# 7_dc_dc_3v3_ant_obdh.net
KiCad netlist of a schematic drawn in Altium Designer
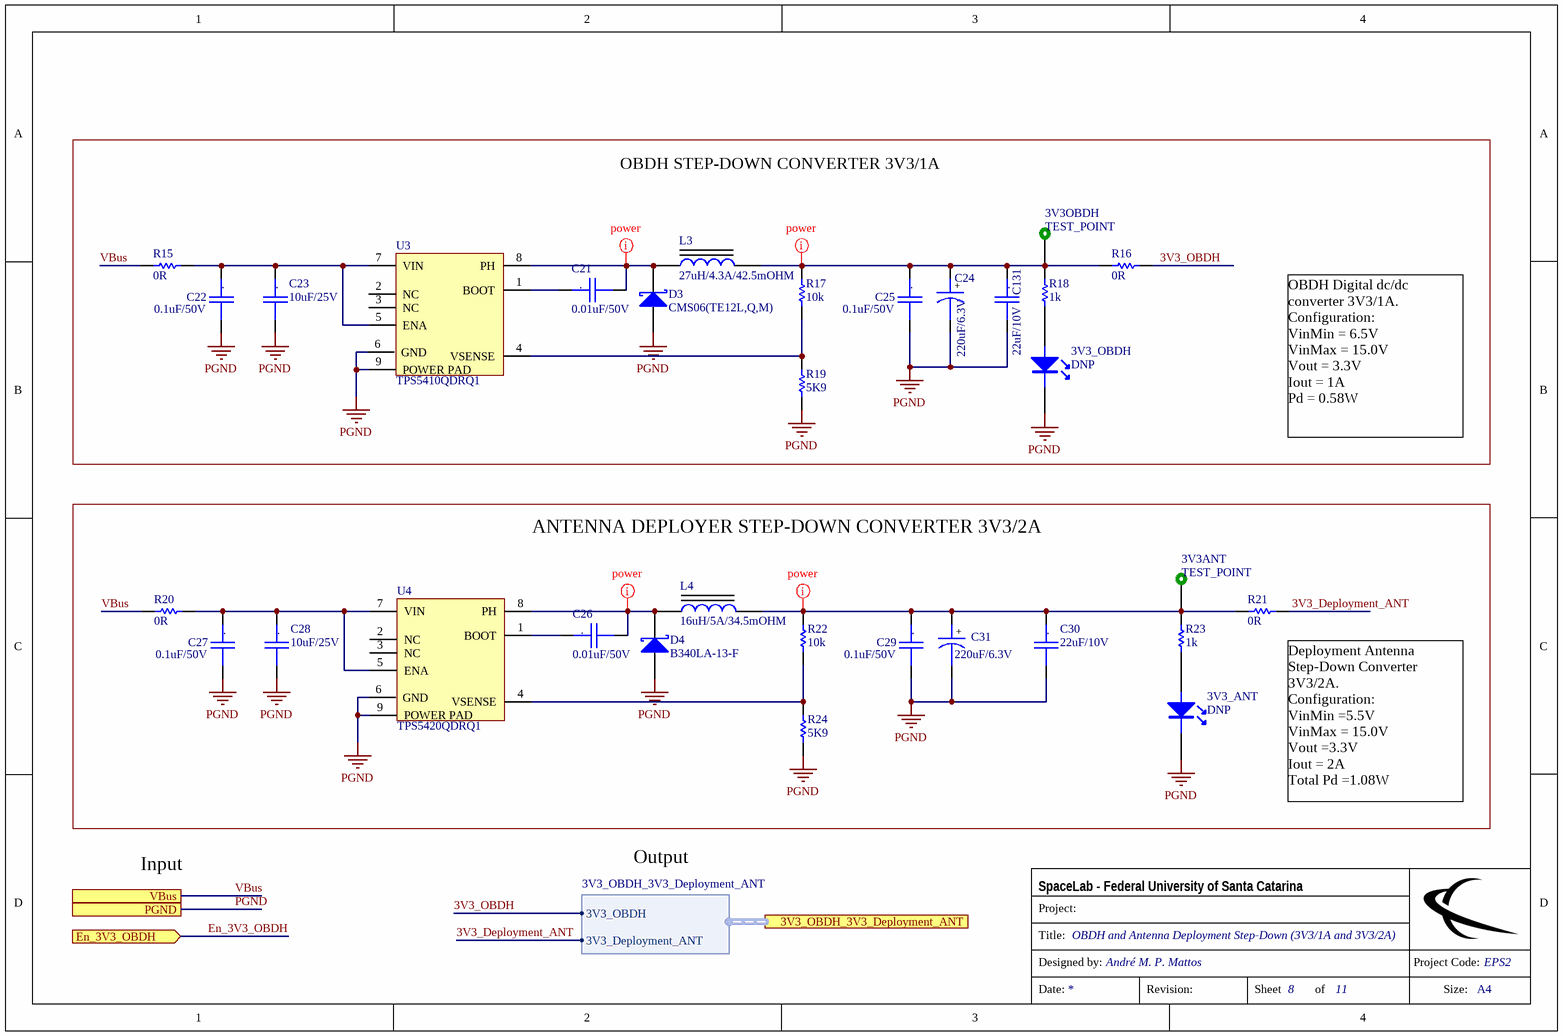
[diagram p0: 7_dc_dc_3v3_ant_obdh.schdoc]

(export (version "E")
  (design (tool "Eeschema 10.0.6"))
  (components
    (comp (ref "3V3ANT")
      (value "TEST_POINT")
      (footprint "TEST_POINT")
      (description "Test point")
      (libsource (lib "PCB_Project_FlightModel_EPS") (part "TEST_POINT"))
    )
    (comp (ref "3V3OBDH")
      (value "TEST_POINT")
      (footprint "TEST_POINT")
      (description "Test point")
      (libsource (lib "PCB_Project_FlightModel_EPS") (part "TEST_POINT"))
    )
    (comp (ref "3V3_ANT")
      (value "DNP")
      (footprint "0603-LED")
      (description "SMD Green LED")
      (fields (field (name "PARTNUMBER") "150060VS75000") (field (name "MANUFACTURER") "Wurth Electronics"))
      (libsource (lib "PCB_Project_FlightModel_EPS") (part "LED/G_0603"))
    )
    (comp (ref "3V3_OBDH")
      (value "DNP")
      (footprint "0603-LED")
      (description "SMD Green LED")
      (fields (field (name "PARTNUMBER") "150060VS75000") (field (name "MANUFACTURER") "Wurth Electronics"))
      (libsource (lib "PCB_Project_FlightModel_EPS") (part "LED/G_0603"))
    )
    (comp (ref "C21")
      (value "0.01uF/50V")
      (footprint "CC0805")
      (description "CAP CER 0.01uF 50V 10% X7R 0805")
      (fields (field (name "PARTNUMBER") "08055C103KAT4A") (field (name "MANUFACTURER") "Kyocera AVX"))
      (libsource (lib "PCB_Project_FlightModel_EPS") (part "Cap_Cer_X7R_0.01uF_50V_0805"))
    )
    (comp (ref "C22")
      (value "0.1uF/50V")
      (footprint "CC0805")
      (description "CAP CER 0.1UF 50V 10% X7R 0805")
      (fields (field (name "PARTNUMBER") "CC0805KRX7R9BB104") (field (name "MANUFACTURER") "Yageo"))
      (libsource (lib "PCB_Project_FlightModel_EPS") (part "Cap_Cer_X7R_0.1uF_50V_0805"))
    )
    (comp (ref "C23")
      (value "10uF/25V")
      (footprint "CC1206")
      (description "CAP CER 10uF 25V 10% X7R 1206")
      (fields (field (name "PARTNUMBER") "GRM31CR71E106KA12L") (field (name "MANUFACTURER") "Murata"))
      (libsource (lib "PCB_Project_FlightModel_EPS") (part "Cap_Cer_X7R_10uF_25V_1206"))
    )
    (comp (ref "C24")
      (value "220uF/6.3V")
      (footprint "FloripaSatPcbLib:cc1210")
      (description "CAP Tantalum 220uF 6.3V 20% 1210")
      (fields (field (name "PARTNUMBER") "6TPE220MAZB") (field (name "MANUFACTURER") "Panasonic"))
      (libsource (lib "PCB_Project_FlightModel_EPS") (part "Cap_Tant_SMD_220uF_6.3V_1210"))
    )
    (comp (ref "C25")
      (value "0.1uF/50V")
      (footprint "CC0805")
      (description "CAP CER 0.1UF 50V 10% X7R 0805")
      (fields (field (name "PARTNUMBER") "CC0805KRX7R9BB104") (field (name "MANUFACTURER") "Yageo"))
      (libsource (lib "PCB_Project_FlightModel_EPS") (part "Cap_Cer_X7R_0.1uF_50V_0805"))
    )
    (comp (ref "C26")
      (value "0.01uF/50V")
      (footprint "CC0805")
      (description "CAP CER 0.01uF 50V 10% X7R 0805")
      (fields (field (name "PARTNUMBER") "08055C103KAT4A") (field (name "MANUFACTURER") "Kyocera AVX"))
      (libsource (lib "PCB_Project_FlightModel_EPS") (part "Cap_Cer_X7R_0.01uF_50V_0805"))
    )
    (comp (ref "C27")
      (value "0.1uF/50V")
      (footprint "CC0805")
      (description "CAP CER 0.1UF 50V 10% X7R 0805")
      (fields (field (name "PARTNUMBER") "CC0805KRX7R9BB104") (field (name "MANUFACTURER") "Yageo"))
      (libsource (lib "PCB_Project_FlightModel_EPS") (part "Cap_Cer_X7R_0.1uF_50V_0805"))
    )
    (comp (ref "C28")
      (value "10uF/25V")
      (footprint "CC1206")
      (description "CAP CER 10uF 25V 10% X7R 1206")
      (fields (field (name "PARTNUMBER") "GRM31CR71E106KA12L") (field (name "MANUFACTURER") "Murata"))
      (libsource (lib "PCB_Project_FlightModel_EPS") (part "Cap_Cer_X7R_10uF_25V_1206"))
    )
    (comp (ref "C29")
      (value "0.1uF/50V")
      (footprint "CC0805")
      (description "CAP CER 0.1UF 50V 10% X7R 0805")
      (fields (field (name "PARTNUMBER") "CC0805KRX7R9BB104") (field (name "MANUFACTURER") "Yageo"))
      (libsource (lib "PCB_Project_FlightModel_EPS") (part "Cap_Cer_X7R_0.1uF_50V_0805"))
    )
    (comp (ref "C30")
      (value "22uF/10V")
      (footprint "CC1206")
      (description "CAP CER 22uF 10V 10% X7R 1206")
      (fields (field (name "PARTNUMBER") "GRM31CR71A226KE15L") (field (name "MANUFACTURER") "Murata"))
      (libsource (lib "PCB_Project_FlightModel_EPS") (part "Cap_Cer_X7R_22uF_10V_1206"))
    )
    (comp (ref "C31")
      (value "220uF/6.3V")
      (footprint "FloripaSatPcbLib:cc1210")
      (description "CAP Tantalum 220uF 6.3V 20% 1210")
      (fields (field (name "PARTNUMBER") "6TPE220MAZB") (field (name "MANUFACTURER") "Panasonic"))
      (libsource (lib "PCB_Project_FlightModel_EPS") (part "Cap_Tant_SMD_220uF_6.3V_1210"))
    )
    (comp (ref "C131")
      (value "22uF/10V")
      (footprint "CC1206")
      (description "CAP CER 22uF 10V 10% X7R 1206")
      (fields (field (name "PARTNUMBER") "GRM31CR71A226KE15L") (field (name "MANUFACTURER") "Murata"))
      (libsource (lib "PCB_Project_FlightModel_EPS") (part "Cap_Cer_X7R_22uF_10V_1206"))
    )
    (comp (ref "D3")
      (value "CMS06(TE12L,Q,M)")
      (footprint "cms06")
      (description "DIODE SCHOTTKY 30V 2A   CMS06(TE12L,Q,M)")
      (fields (field (name "MANUFACTURER") "Toshiba"))
      (libsource (lib "PCB_Project_FlightModel_EPS") (part "DIODE_SCHOTTKY_30V_2A_  CMS06(TE12L,Q,M)"))
    )
    (comp (ref "D4")
      (value "B340LA-13-F")
      (footprint "DO-214AC")
      (description "DIODE SCHOTTKY 40V 3A B340LA-13-F")
      (fields (field (name "MANUFACTURER") "Diodes"))
      (libsource (lib "PCB_Project_FlightModel_EPS") (part "DIODE_SCHOTTKY_40V_3A_B340LA-13-F"))
    )
    (comp (ref "L3")
      (value "27uH/4.3A/42.5mOHM")
      (footprint "IND_744325xxx")
      (description "INDUCTOR 27UH 4.3A SMD")
      (fields (field (name "PARTNUMBER") "7447798271") (field (name "MANUFACTURER") "Wurth Electronics"))
      (libsource (lib "PCB_Project_FlightModel_EPS") (part "IND_POWER_27uH_4.3A_42.5mR"))
    )
    (comp (ref "L4")
      (value "16uH/5A/34.5mOHM")
      (footprint "IND_744325xxx")
      (description "INDUCTOR 16UH 5A SMD")
      (fields (field (name "PARTNUMBER") "7443251600") (field (name "MANUFACTURER") "Wurth Electronics"))
      (libsource (lib "PCB_Project_FlightModel_EPS") (part "IND_POWER_16uH_5A_35.5mR"))
    )
    (comp (ref "R15")
      (value "0R")
      (footprint "1206")
      (description "RES 0.0 OHM 3/4W JUMP 1206")
      (fields
        (field (name "PARTNUMBER") "HCJ1206ZT0R00")
        (field (name "MANUFACTURER") "Stackpole Electronics")
      )
      (libsource (lib "PCB_Project_FlightModel_EPS") (part "R0R_JUMPER_3/4W_1206"))
    )
    (comp (ref "R16")
      (value "0R")
      (footprint "1206")
      (description "RES 0.0 OHM 3/4W JUMP 1206")
      (fields
        (field (name "PARTNUMBER") "HCJ1206ZT0R00")
        (field (name "MANUFACTURER") "Stackpole Electronics")
      )
      (libsource (lib "PCB_Project_FlightModel_EPS") (part "R0R_JUMPER_3/4W_1206"))
    )
    (comp (ref "R17")
      (value "10k")
      (footprint "0805")
      (description "RES 10K OHM 1/8W 1%  0805")
      (fields (field (name "PARTNUMBER") "CRCW080510K0FKEA") (field (name "MANUFACTURER") "Vishay"))
      (libsource (lib "PCB_Project_FlightModel_EPS") (part "R10k_1%_1/8W_0805"))
    )
    (comp (ref "R18")
      (value "1k")
      (footprint "0603")
      (description "RES 1.0K OHM 1/8W 1% 0603")
      (fields (field (name "PARTNUMBER") "MCT06030C1001FP500") (field (name "MANUFACTURER") "Vishay"))
      (libsource (lib "PCB_Project_FlightModel_EPS") (part "R1.0k_1%_1/8W_0603"))
    )
    (comp (ref "R19")
      (value "5K9")
      (footprint "0805")
      (description "RES 5K9 OHM 1/8W 1% 0805")
      (fields (field (name "PARTNUMBER") "71-CRCW0805-5.9K-E3") (field (name "MANUFACTURER") "Vishay"))
      (libsource (lib "PCB_Project_FlightModel_EPS") (part "R5.9K_1%_1/8W_0805"))
    )
    (comp (ref "R20")
      (value "0R")
      (footprint "1206")
      (description "RES 0.0 OHM 3/4W JUMP 1206")
      (fields
        (field (name "PARTNUMBER") "HCJ1206ZT0R00")
        (field (name "MANUFACTURER") "Stackpole Electronics")
      )
      (libsource (lib "PCB_Project_FlightModel_EPS") (part "R0R_JUMPER_3/4W_1206"))
    )
    (comp (ref "R21")
      (value "0R")
      (footprint "1206")
      (description "RES 0.0 OHM 3/4W JUMP 1206")
      (fields
        (field (name "PARTNUMBER") "HCJ1206ZT0R00")
        (field (name "MANUFACTURER") "Stackpole Electronics")
      )
      (libsource (lib "PCB_Project_FlightModel_EPS") (part "R0R_JUMPER_3/4W_1206"))
    )
    (comp (ref "R22")
      (value "10k")
      (footprint "0805")
      (description "RES 10K OHM 1/8W 1%  0805")
      (fields (field (name "PARTNUMBER") "CRCW080510K0FKEA") (field (name "MANUFACTURER") "Vishay"))
      (libsource (lib "PCB_Project_FlightModel_EPS") (part "R10k_1%_1/8W_0805"))
    )
    (comp (ref "R23")
      (value "1k")
      (footprint "0603")
      (description "RES 1.0K OHM 1/8W 1% 0603")
      (fields (field (name "PARTNUMBER") "MCT06030C1001FP500") (field (name "MANUFACTURER") "Vishay"))
      (libsource (lib "PCB_Project_FlightModel_EPS") (part "R1.0k_1%_1/8W_0603"))
    )
    (comp (ref "R24")
      (value "5K9")
      (footprint "0805")
      (description "RES 5K9 OHM 1/8W 1% 0805")
      (fields (field (name "PARTNUMBER") "71-CRCW0805-5.9K-E3") (field (name "MANUFACTURER") "Vishay"))
      (libsource (lib "PCB_Project_FlightModel_EPS") (part "R5.9K_1%_1/8W_0805"))
    )
    (comp (ref "U3")
      (value "TPS5410QDRQ1")
      (footprint "SO8 Power PAD")
      (fields (field (name "MANUFACTURER") "Texas Instruments"))
      (libsource (lib "PCB_Project_FlightModel_EPS") (part "TPS5410QDRQ1"))
    )
    (comp (ref "U4")
      (value "TPS5420QDRQ1")
      (footprint "SO8 Power PAD")
      (fields (field (name "MANUFACTURER") "Texas Instruments"))
      (libsource (lib "PCB_Project_FlightModel_EPS") (part "TPS5420QDRQ1"))
    )
  )
  (nets
    (net (code "2") (name "/3V3_Deployment_ANT") (class "Default")
      (node (ref "R21") (pin "1") (pinfunction "1_1") (pintype "passive"))
    )
    (net (code "3") (name "/3V3_OBDH") (class "Default")
      (node (ref "R16") (pin "1") (pinfunction "1_1") (pintype "passive"))
    )
    (net (code "5") (name "/VBus") (class "Default")
      (node (ref "R15") (pin "2") (pinfunction "2_2") (pintype "passive"))
      (node (ref "R20") (pin "2") (pinfunction "2_2") (pintype "passive"))
    )
    (net (code "7") (name "Net-(3V3ANT-Pad1)") (class "Default")
      (node (ref "3V3ANT") (pin "1") (pinfunction "1_1") (pintype "passive"))
      (node (ref "C29") (pin "1") (pinfunction "1_1") (pintype "passive"))
      (node (ref "C30") (pin "1") (pinfunction "1_1") (pintype "passive"))
      (node (ref "C31") (pin "1") (pinfunction "1_1") (pintype "passive"))
      (node (ref "L4") (pin "2") (pinfunction "2_2") (pintype "passive"))
      (node (ref "R21") (pin "2") (pinfunction "2_2") (pintype "passive"))
      (node (ref "R22") (pin "2") (pinfunction "2_2") (pintype "passive"))
      (node (ref "R23") (pin "1") (pinfunction "1_1") (pintype "passive"))
    )
    (net (code "8") (name "Net-(3V3OBDH-Pad1)") (class "Default")
      (node (ref "3V3OBDH") (pin "1") (pinfunction "1_1") (pintype "passive"))
      (node (ref "C131") (pin "1") (pinfunction "1_1") (pintype "passive"))
      (node (ref "C24") (pin "1") (pinfunction "1_1") (pintype "passive"))
      (node (ref "C25") (pin "1") (pinfunction "1_1") (pintype "passive"))
      (node (ref "L3") (pin "2") (pinfunction "2_2") (pintype "passive"))
      (node (ref "R16") (pin "2") (pinfunction "2_2") (pintype "passive"))
      (node (ref "R17") (pin "2") (pinfunction "2_2") (pintype "passive"))
      (node (ref "R18") (pin "1") (pinfunction "1_1") (pintype "passive"))
    )
    (net (code "9") (name "Net-(3V3_ANT-A)") (class "Default")
      (node (ref "3V3_ANT") (pin "1") (pinfunction "A_1") (pintype "passive"))
      (node (ref "R23") (pin "2") (pinfunction "2_2") (pintype "passive"))
    )
    (net (code "10") (name "Net-(3V3_OBDH-A)") (class "Default")
      (node (ref "3V3_OBDH") (pin "1") (pinfunction "A_1") (pintype "passive"))
      (node (ref "R18") (pin "2") (pinfunction "2_2") (pintype "passive"))
    )
    (net (code "11") (name "Net-(D3-K)") (class "Default")
      (node (ref "C21") (pin "2") (pinfunction "2_2") (pintype "passive"))
      (node (ref "D3") (pin "1") (pinfunction "K_1") (pintype "passive"))
      (node (ref "L3") (pin "1") (pinfunction "1_1") (pintype "passive"))
      (node (ref "U3") (pin "8") (pinfunction "PH_8") (pintype "passive"))
    )
    (net (code "12") (name "Net-(D4-K)") (class "Default")
      (node (ref "C26") (pin "2") (pinfunction "2_2") (pintype "passive"))
      (node (ref "D4") (pin "1") (pinfunction "K_1") (pintype "passive"))
      (node (ref "L4") (pin "1") (pinfunction "1_1") (pintype "passive"))
      (node (ref "U4") (pin "8") (pinfunction "PH_8") (pintype "passive"))
    )
    (net (code "13") (name "Net-(U3-BOOT)") (class "Default")
      (node (ref "C21") (pin "1") (pinfunction "1_1") (pintype "passive"))
      (node (ref "U3") (pin "1") (pinfunction "BOOT_1") (pintype "passive"))
    )
    (net (code "14") (name "Net-(U3-ENA)") (class "Default")
      (node (ref "C22") (pin "1") (pinfunction "1_1") (pintype "passive"))
      (node (ref "C23") (pin "1") (pinfunction "1_1") (pintype "passive"))
      (node (ref "R15") (pin "1") (pinfunction "1_1") (pintype "passive"))
      (node (ref "U3") (pin "5") (pinfunction "ENA_5") (pintype "passive"))
      (node (ref "U3") (pin "7") (pinfunction "VIN_7") (pintype "passive"))
    )
    (net (code "15") (name "Net-(U3-VSENSE)") (class "Default")
      (node (ref "R17") (pin "1") (pinfunction "1_1") (pintype "passive"))
      (node (ref "R19") (pin "2") (pinfunction "2_2") (pintype "passive"))
      (node (ref "U3") (pin "4") (pinfunction "VSENSE_4") (pintype "passive"))
    )
    (net (code "16") (name "Net-(U4-BOOT)") (class "Default")
      (node (ref "C26") (pin "1") (pinfunction "1_1") (pintype "passive"))
      (node (ref "U4") (pin "1") (pinfunction "BOOT_1") (pintype "passive"))
    )
    (net (code "17") (name "Net-(U4-ENA)") (class "Default")
      (node (ref "C27") (pin "1") (pinfunction "1_1") (pintype "passive"))
      (node (ref "C28") (pin "1") (pinfunction "1_1") (pintype "passive"))
      (node (ref "R20") (pin "1") (pinfunction "1_1") (pintype "passive"))
      (node (ref "U4") (pin "5") (pinfunction "ENA_5") (pintype "passive"))
      (node (ref "U4") (pin "7") (pinfunction "VIN_7") (pintype "passive"))
    )
    (net (code "18") (name "Net-(U4-VSENSE)") (class "Default")
      (node (ref "R22") (pin "1") (pinfunction "1_1") (pintype "passive"))
      (node (ref "R24") (pin "2") (pinfunction "2_2") (pintype "passive"))
      (node (ref "U4") (pin "4") (pinfunction "VSENSE_4") (pintype "passive"))
    )
    (net (code "19") (name "PGND") (class "Default")
      (node (ref "3V3_ANT") (pin "2") (pinfunction "K_2") (pintype "passive"))
      (node (ref "3V3_OBDH") (pin "2") (pinfunction "K_2") (pintype "passive"))
      (node (ref "C131") (pin "2") (pinfunction "2_2") (pintype "passive"))
      (node (ref "C22") (pin "2") (pinfunction "2_2") (pintype "passive"))
      (node (ref "C23") (pin "2") (pinfunction "2_2") (pintype "passive"))
      (node (ref "C24") (pin "2") (pinfunction "2_2") (pintype "passive"))
      (node (ref "C25") (pin "2") (pinfunction "2_2") (pintype "passive"))
      (node (ref "C27") (pin "2") (pinfunction "2_2") (pintype "passive"))
      (node (ref "C28") (pin "2") (pinfunction "2_2") (pintype "passive"))
      (node (ref "C29") (pin "2") (pinfunction "2_2") (pintype "passive"))
      (node (ref "C30") (pin "2") (pinfunction "2_2") (pintype "passive"))
      (node (ref "C31") (pin "2") (pinfunction "2_2") (pintype "passive"))
      (node (ref "D3") (pin "2") (pinfunction "A_2") (pintype "passive"))
      (node (ref "D4") (pin "2") (pinfunction "A_2") (pintype "passive"))
      (node (ref "R19") (pin "1") (pinfunction "1_1") (pintype "passive"))
      (node (ref "R24") (pin "1") (pinfunction "1_1") (pintype "passive"))
      (node (ref "U3") (pin "6") (pinfunction "GND_6") (pintype "passive"))
      (node (ref "U3") (pin "9") (pinfunction "POWER_PAD_9") (pintype "passive"))
      (node (ref "U4") (pin "6") (pinfunction "GND_6") (pintype "passive"))
      (node (ref "U4") (pin "9") (pinfunction "POWER_PAD_9") (pintype "passive"))
    )
    (net (code "20") (name "unconnected-(U3-NC-Pad2)") (class "Default")
      (node (ref "U3") (pin "2") (pinfunction "NC_2") (pintype "passive"))
    )
    (net (code "21") (name "unconnected-(U3-NC-Pad3)") (class "Default")
      (node (ref "U3") (pin "3") (pinfunction "NC_3") (pintype "passive"))
    )
    (net (code "22") (name "unconnected-(U4-NC-Pad2)") (class "Default")
      (node (ref "U4") (pin "2") (pinfunction "NC_2") (pintype "passive"))
    )
    (net (code "23") (name "unconnected-(U4-NC-Pad3)") (class "Default")
      (node (ref "U4") (pin "3") (pinfunction "NC_3") (pintype "passive"))
    )
  )
)
